# Splitter.net
KiCad netlist of a schematic drawn in EAGLE
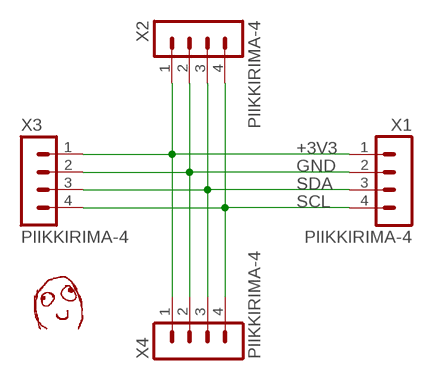
[diagram p0: schematic, sheet 1]

(export (version "E")
  (design (tool "Eeschema 10.0.6"))
  (components
    (comp (ref "U$1")
      (value "DAFUG")
      (footprint "eagle-import:DAFUG")
      (libsource (lib "eagle-import") (part "DAFUG"))
    )
    (comp (ref "X1")
      (value "PIIKKIRIMA-4")
      (footprint "eagle-import:PIIKKIRIMA-4")
      (libsource (lib "eagle-import") (part "PIIKKIRIMA-4"))
    )
    (comp (ref "X2")
      (value "PIIKKIRIMA-4")
      (footprint "eagle-import:PIIKKIRIMA-4")
      (libsource (lib "eagle-import") (part "PIIKKIRIMA-4"))
    )
    (comp (ref "X3")
      (value "PIIKKIRIMA-4")
      (footprint "eagle-import:PIIKKIRIMA-4")
      (libsource (lib "eagle-import") (part "PIIKKIRIMA-4"))
    )
    (comp (ref "X4")
      (value "PIIKKIRIMA-4")
      (footprint "eagle-import:PIIKKIRIMA-4")
      (libsource (lib "eagle-import") (part "PIIKKIRIMA-4"))
    )
  )
  (nets
    (net (code "1") (name "/+3V3") (class "Default")
      (node (ref "X1") (pin "1") (pinfunction "1_1") (pintype "passive"))
      (node (ref "X2") (pin "1") (pinfunction "1_1") (pintype "passive"))
      (node (ref "X3") (pin "1") (pinfunction "1_1") (pintype "passive"))
      (node (ref "X4") (pin "1") (pinfunction "1_1") (pintype "passive"))
    )
    (net (code "2") (name "/GND") (class "Default")
      (node (ref "X1") (pin "2") (pinfunction "2_2") (pintype "passive"))
      (node (ref "X2") (pin "2") (pinfunction "2_2") (pintype "passive"))
      (node (ref "X3") (pin "2") (pinfunction "2_2") (pintype "passive"))
      (node (ref "X4") (pin "2") (pinfunction "2_2") (pintype "passive"))
    )
    (net (code "3") (name "/SCL") (class "Default")
      (node (ref "X1") (pin "4") (pinfunction "4_4") (pintype "passive"))
      (node (ref "X2") (pin "4") (pinfunction "4_4") (pintype "passive"))
      (node (ref "X3") (pin "4") (pinfunction "4_4") (pintype "passive"))
      (node (ref "X4") (pin "4") (pinfunction "4_4") (pintype "passive"))
    )
    (net (code "4") (name "/SDA") (class "Default")
      (node (ref "X1") (pin "3") (pinfunction "3_3") (pintype "passive"))
      (node (ref "X2") (pin "3") (pinfunction "3_3") (pintype "passive"))
      (node (ref "X3") (pin "3") (pinfunction "3_3") (pintype "passive"))
      (node (ref "X4") (pin "3") (pinfunction "3_3") (pintype "passive"))
    )
  )
)
